# main.net
KiCad netlist of a schematic drawn in EAGLE
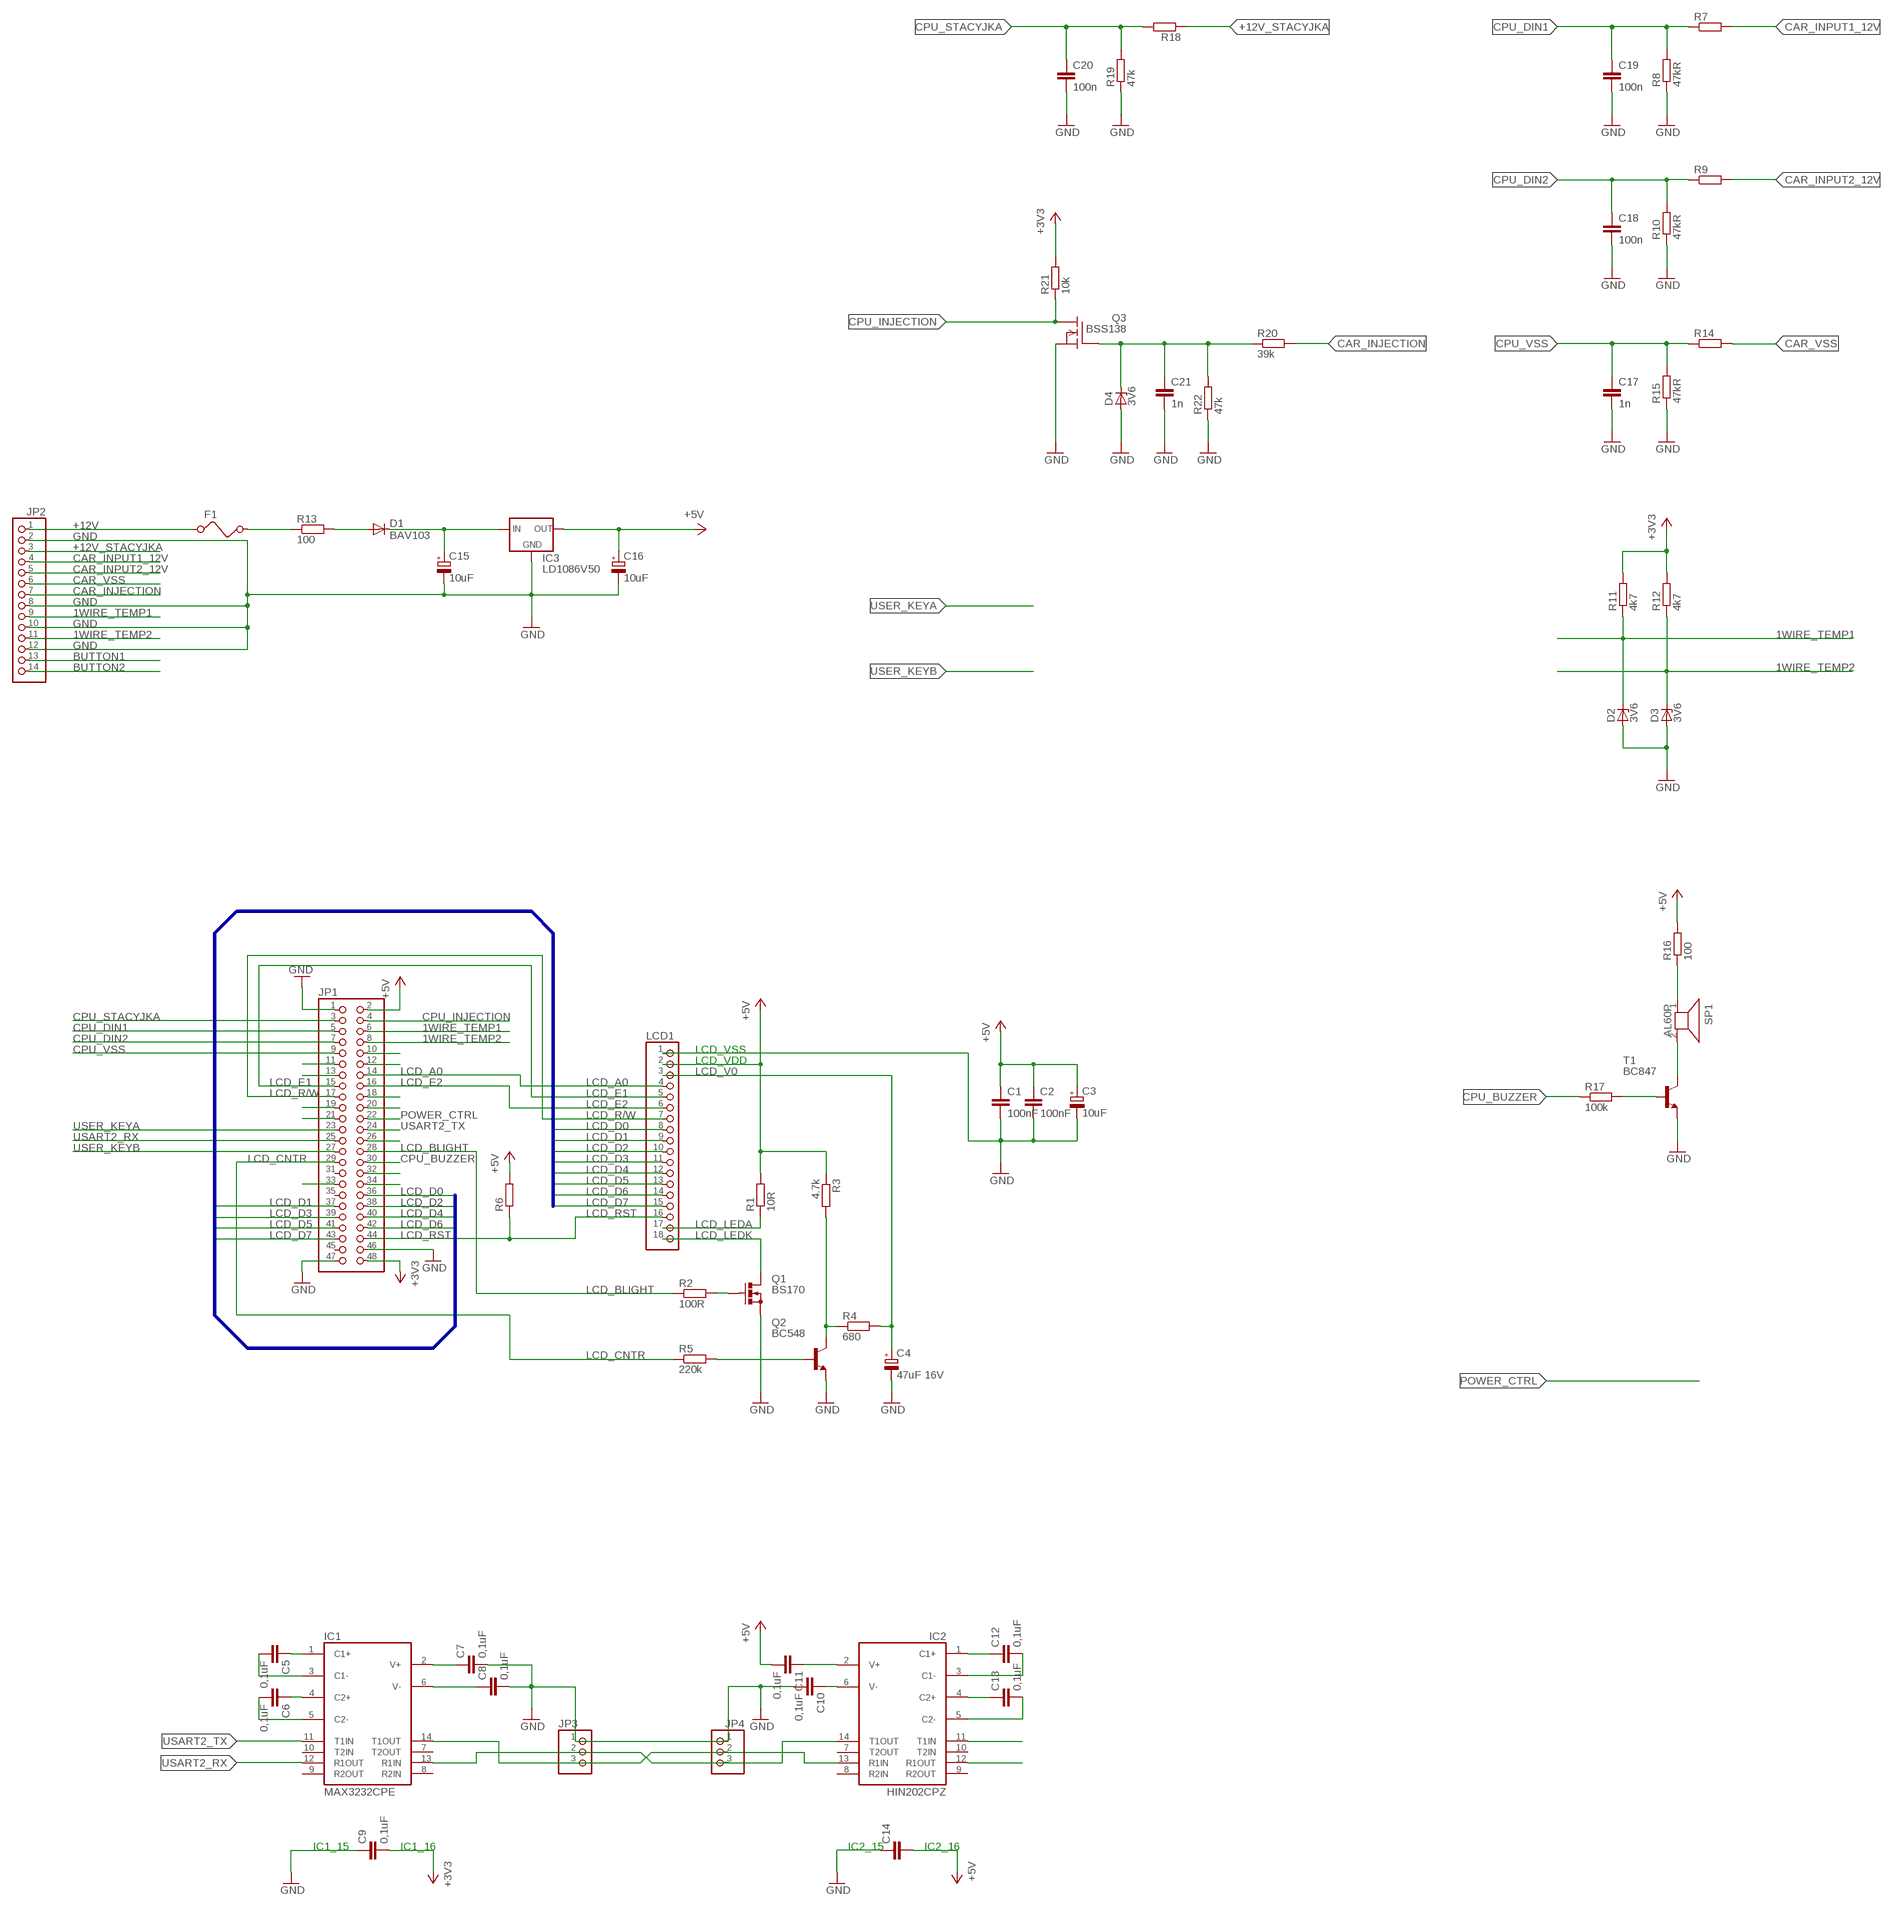
[diagram p0: schematic, sheet 1]

(export (version "E")
  (design (tool "Eeschema 10.0.6"))
  (components
    (comp (ref "C1")
      (value "100nF")
      (footprint "eagle-import:C025-024X044")
      (libsource (lib "eagle-import") (part "C-EU025-024X044"))
    )
    (comp (ref "C2")
      (value "100nF")
      (footprint "eagle-import:C025-024X044")
      (libsource (lib "eagle-import") (part "C-EU025-024X044"))
    )
    (comp (ref "C3")
      (value "10uF")
      (footprint "eagle-import:085CS_1AR")
      (libsource (lib "eagle-import") (part "CPOL-EU085CS-1AR"))
    )
    (comp (ref "C4")
      (value "47uF 16V")
      (footprint "eagle-import:085CS_1AR")
      (libsource (lib "eagle-import") (part "CPOL-EU085CS-1AR"))
    )
    (comp (ref "C5")
      (value "0,1uF")
      (footprint "eagle-import:C025-024X044")
      (libsource (lib "eagle-import") (part "C-EU025-024X044"))
    )
    (comp (ref "C6")
      (value "0,1uF")
      (footprint "eagle-import:C025-024X044")
      (libsource (lib "eagle-import") (part "C-EU025-024X044"))
    )
    (comp (ref "C7")
      (value "0,1uF")
      (footprint "eagle-import:C025-024X044")
      (libsource (lib "eagle-import") (part "C-EU025-024X044"))
    )
    (comp (ref "C8")
      (value "0,1uF")
      (footprint "eagle-import:C025-024X044")
      (libsource (lib "eagle-import") (part "C-EU025-024X044"))
    )
    (comp (ref "C9")
      (value "0,1uF")
      (footprint "eagle-import:C025-024X044")
      (libsource (lib "eagle-import") (part "C-EU025-024X044"))
    )
    (comp (ref "C10")
      (value "0,1uF")
      (footprint "eagle-import:C025-024X044")
      (libsource (lib "eagle-import") (part "C-EU025-024X044"))
    )
    (comp (ref "C11")
      (value "0,1uF")
      (footprint "eagle-import:C025-024X044")
      (libsource (lib "eagle-import") (part "C-EU025-024X044"))
    )
    (comp (ref "C12")
      (value "0,1uF")
      (footprint "eagle-import:C025-024X044")
      (libsource (lib "eagle-import") (part "C-EU025-024X044"))
    )
    (comp (ref "C13")
      (value "0,1uF")
      (footprint "eagle-import:C025-024X044")
      (libsource (lib "eagle-import") (part "C-EU025-024X044"))
    )
    (comp (ref "C14")
      (value "C-EU025-024X044")
      (footprint "eagle-import:C025-024X044")
      (libsource (lib "eagle-import") (part "C-EU025-024X044"))
    )
    (comp (ref "C15")
      (value "10uF")
      (footprint "eagle-import:085CS_1AR")
      (libsource (lib "eagle-import") (part "CPOL-EU085CS-1AR"))
    )
    (comp (ref "C16")
      (value "10uF")
      (footprint "eagle-import:085CS_1AR")
      (libsource (lib "eagle-import") (part "CPOL-EU085CS-1AR"))
    )
    (comp (ref "C17")
      (value "1n")
      (footprint "eagle-import:C025-024X044")
      (libsource (lib "eagle-import") (part "C-EU025-024X044"))
    )
    (comp (ref "C18")
      (value "100n")
      (footprint "eagle-import:C025-024X044")
      (libsource (lib "eagle-import") (part "C-EU025-024X044"))
    )
    (comp (ref "C19")
      (value "100n")
      (footprint "eagle-import:C025-024X044")
      (libsource (lib "eagle-import") (part "C-EU025-024X044"))
    )
    (comp (ref "C20")
      (value "100n")
      (footprint "eagle-import:C025-024X044")
      (libsource (lib "eagle-import") (part "C-EU025-024X044"))
    )
    (comp (ref "C21")
      (value "1n")
      (footprint "eagle-import:C025-024X044")
      (libsource (lib "eagle-import") (part "C-EU025-024X044"))
    )
    (comp (ref "D1")
      (value "BAV103")
      (footprint "eagle-import:DO41-10")
      (libsource (lib "eagle-import") (part "1N4004"))
    )
    (comp (ref "D2")
      (value "3V6")
      (footprint "eagle-import:C1702-15")
      (libsource (lib "eagle-import") (part "ZENER-DIODEC1702-15"))
    )
    (comp (ref "D3")
      (value "3V6")
      (footprint "eagle-import:C1702-15")
      (libsource (lib "eagle-import") (part "ZENER-DIODEC1702-15"))
    )
    (comp (ref "D4")
      (value "3V6")
      (footprint "eagle-import:C1702-15")
      (libsource (lib "eagle-import") (part "ZENER-DIODEC1702-15"))
    )
    (comp (ref "F1")
      (value "FUSE")
      (footprint "eagle-import:FUSE")
      (libsource (lib "eagle-import") (part "FUSE"))
    )
    (comp (ref "IC1")
      (value "MAX3232CPE")
      (footprint "eagle-import:DIL16")
      (fields (field (name "MF") "MAXIM") (field (name "MPN") "MAX3232CPE+"))
      (libsource (lib "eagle-import") (part "MAX3232PEC"))
    )
    (comp (ref "IC2")
      (value "HIN202CPZ")
      (footprint "eagle-import:DIL16")
      (fields (field (name "MF") "MAXIM") (field (name "MPN") "MAX3232CPE+"))
      (libsource (lib "eagle-import") (part "MAX3232PEC"))
    )
    (comp (ref "IC3")
      (value "LD1086V50")
      (footprint "eagle-import:78MXXL")
      (libsource (lib "eagle-import") (part "78MXXL"))
    )
    (comp (ref "JP1")
      (value "PINHD-2X24")
      (footprint "eagle-import:2X24")
      (libsource (lib "eagle-import") (part "PINHD-2X24"))
    )
    (comp (ref "JP2")
      (value "PINHD-1X14")
      (footprint "eagle-import:1X14")
      (libsource (lib "eagle-import") (part "PINHD-1X14"))
    )
    (comp (ref "JP3")
      (value "PINHD-1X3")
      (footprint "eagle-import:1X03")
      (libsource (lib "eagle-import") (part "PINHD-1X3"))
    )
    (comp (ref "JP4")
      (value "PINHD-1X3")
      (footprint "eagle-import:1X03")
      (libsource (lib "eagle-import") (part "PINHD-1X3"))
    )
    (comp (ref "LCD1")
      (value "PINHD-1X18")
      (footprint "eagle-import:1X18")
      (libsource (lib "eagle-import") (part "PINHD-1X18"))
    )
    (comp (ref "Q1")
      (value "BS170")
      (footprint "eagle-import:SOT54E")
      (libsource (lib "eagle-import") (part "BS170"))
    )
    (comp (ref "Q2")
      (value "BC548")
      (footprint "eagle-import:TO92-EBC")
      (libsource (lib "eagle-import") (part "BC548"))
    )
    (comp (ref "Q3")
      (value "BSS138")
      (footprint "eagle-import:TO92")
      (libsource (lib "eagle-import") (part "BSS101"))
    )
    (comp (ref "R1")
      (value "10R")
      (footprint "eagle-import:0204V")
      (libsource (lib "eagle-import") (part "R-EU_0204/2V"))
    )
    (comp (ref "R2")
      (value "100R")
      (footprint "eagle-import:0204V")
      (libsource (lib "eagle-import") (part "R-EU_0204/2V"))
    )
    (comp (ref "R3")
      (value "4.7k")
      (footprint "eagle-import:0204V")
      (libsource (lib "eagle-import") (part "R-EU_0204/2V"))
    )
    (comp (ref "R4")
      (value "680")
      (footprint "eagle-import:0204V")
      (libsource (lib "eagle-import") (part "R-EU_0204/2V"))
    )
    (comp (ref "R5")
      (value "220k")
      (footprint "eagle-import:0204V")
      (libsource (lib "eagle-import") (part "R-EU_0204/2V"))
    )
    (comp (ref "R6")
      (value "R-EU_0204/2V")
      (footprint "eagle-import:0204V")
      (libsource (lib "eagle-import") (part "R-EU_0204/2V"))
    )
    (comp (ref "R7")
      (value "R-EU_0204/2V")
      (footprint "eagle-import:0204V")
      (libsource (lib "eagle-import") (part "R-EU_0204/2V"))
    )
    (comp (ref "R8")
      (value "47kR")
      (footprint "eagle-import:0204V")
      (libsource (lib "eagle-import") (part "R-EU_0204/2V"))
    )
    (comp (ref "R9")
      (value "R-EU_0204/2V")
      (footprint "eagle-import:0204V")
      (libsource (lib "eagle-import") (part "R-EU_0204/2V"))
    )
    (comp (ref "R10")
      (value "47kR")
      (footprint "eagle-import:0204V")
      (libsource (lib "eagle-import") (part "R-EU_0204/2V"))
    )
    (comp (ref "R11")
      (value "4k7")
      (footprint "eagle-import:0204V")
      (libsource (lib "eagle-import") (part "R-EU_0204/2V"))
    )
    (comp (ref "R12")
      (value "4k7")
      (footprint "eagle-import:0204V")
      (libsource (lib "eagle-import") (part "R-EU_0204/2V"))
    )
    (comp (ref "R13")
      (value "100")
      (footprint "eagle-import:0204V")
      (libsource (lib "eagle-import") (part "R-EU_0204/2V"))
    )
    (comp (ref "R14")
      (value "R-EU_0204/2V")
      (footprint "eagle-import:0204V")
      (libsource (lib "eagle-import") (part "R-EU_0204/2V"))
    )
    (comp (ref "R15")
      (value "47kR")
      (footprint "eagle-import:0204V")
      (libsource (lib "eagle-import") (part "R-EU_0204/2V"))
    )
    (comp (ref "R16")
      (value "100")
      (footprint "eagle-import:0204V")
      (libsource (lib "eagle-import") (part "R-EU_0204/2V"))
    )
    (comp (ref "R17")
      (value "100k")
      (footprint "eagle-import:0204V")
      (libsource (lib "eagle-import") (part "R-EU_0204/2V"))
    )
    (comp (ref "R18")
      (value "R-EU_0204/2V")
      (footprint "eagle-import:0204V")
      (libsource (lib "eagle-import") (part "R-EU_0204/2V"))
    )
    (comp (ref "R19")
      (value "47k")
      (footprint "eagle-import:0204V")
      (libsource (lib "eagle-import") (part "R-EU_0204/2V"))
    )
    (comp (ref "R20")
      (value "39k")
      (footprint "eagle-import:0204V")
      (libsource (lib "eagle-import") (part "R-EU_0204/2V"))
    )
    (comp (ref "R21")
      (value "10k")
      (footprint "eagle-import:0204V")
      (libsource (lib "eagle-import") (part "R-EU_0204/2V"))
    )
    (comp (ref "R22")
      (value "47k")
      (footprint "eagle-import:0204V")
      (libsource (lib "eagle-import") (part "R-EU_0204/2V"))
    )
    (comp (ref "SP1")
      (value "AL60P")
      (footprint "eagle-import:AL60P")
      (libsource (lib "eagle-import") (part "AL60P"))
    )
    (comp (ref "T1")
      (value "BC847")
      (footprint "eagle-import:SOT23")
      (libsource (lib "eagle-import") (part "BC847"))
    )
  )
  (nets
    (net (code "1") (name "+3V3") (class "Default")
      (node (ref "C9") (pin "2") (pinfunction "2_2") (pintype "passive"))
      (node (ref "JP1") (pin "48") (pinfunction "48_48") (pintype "passive"))
      (node (ref "R11") (pin "2") (pinfunction "2_2") (pintype "passive"))
      (node (ref "R12") (pin "2") (pinfunction "2_2") (pintype "passive"))
      (node (ref "R21") (pin "2") (pinfunction "2_2") (pintype "passive"))
    )
    (net (code "2") (name "+5V") (class "Default")
      (node (ref "C1") (pin "1") (pinfunction "1_1") (pintype "passive"))
      (node (ref "C11") (pin "2") (pinfunction "2_2") (pintype "passive"))
      (node (ref "C14") (pin "2") (pinfunction "2_2") (pintype "passive"))
      (node (ref "C16") (pin "+") (pinfunction "+_+") (pintype "passive"))
      (node (ref "C2") (pin "1") (pinfunction "1_1") (pintype "passive"))
      (node (ref "C3") (pin "+") (pinfunction "+_+") (pintype "passive"))
      (node (ref "IC3") (pin "OUT") (pinfunction "OUT_OUT") (pintype "passive"))
      (node (ref "JP1") (pin "2") (pinfunction "2_2") (pintype "passive"))
      (node (ref "LCD1") (pin "2") (pinfunction "2_2") (pintype "passive"))
      (node (ref "R1") (pin "2") (pinfunction "2_2") (pintype "passive"))
      (node (ref "R16") (pin "2") (pinfunction "2_2") (pintype "passive"))
      (node (ref "R3") (pin "1") (pinfunction "1_1") (pintype "passive"))
      (node (ref "R6") (pin "2") (pinfunction "2_2") (pintype "passive"))
    )
    (net (code "3") (name "+12V_STACYJKA") (class "Default")
      (node (ref "JP2") (pin "3") (pinfunction "3_3") (pintype "passive"))
      (node (ref "R18") (pin "1") (pinfunction "1_1") (pintype "passive"))
    )
    (net (code "4") (name "/+12V") (class "Default")
      (node (ref "F1") (pin "1") (pinfunction "1_1") (pintype "passive"))
      (node (ref "JP2") (pin "1") (pinfunction "1_1") (pintype "passive"))
    )
    (net (code "5") (name "/1WIRE_TEMP1") (class "Default")
      (node (ref "D2") (pin "C") (pinfunction "C_C") (pintype "passive"))
      (node (ref "JP1") (pin "6") (pinfunction "6_6") (pintype "passive"))
      (node (ref "JP2") (pin "9") (pinfunction "9_9") (pintype "passive"))
      (node (ref "R11") (pin "1") (pinfunction "1_1") (pintype "passive"))
    )
    (net (code "6") (name "/1WIRE_TEMP2") (class "Default")
      (node (ref "D3") (pin "C") (pinfunction "C_C") (pintype "passive"))
      (node (ref "JP1") (pin "8") (pinfunction "8_8") (pintype "passive"))
      (node (ref "JP2") (pin "11") (pinfunction "11_11") (pintype "passive"))
      (node (ref "R12") (pin "1") (pinfunction "1_1") (pintype "passive"))
    )
    (net (code "7") (name "/BUTTON1") (class "Default")
      (node (ref "JP2") (pin "13") (pinfunction "13_13") (pintype "passive"))
    )
    (net (code "8") (name "/BUTTON2") (class "Default")
      (node (ref "JP2") (pin "14") (pinfunction "14_14") (pintype "passive"))
    )
    (net (code "9") (name "/LCD_A0") (class "Default")
      (node (ref "JP1") (pin "14") (pinfunction "14_14") (pintype "passive"))
      (node (ref "LCD1") (pin "4") (pinfunction "4_4") (pintype "passive"))
    )
    (net (code "10") (name "/LCD_BLIGHT") (class "Default")
      (node (ref "JP1") (pin "28") (pinfunction "28_28") (pintype "passive"))
      (node (ref "R2") (pin "1") (pinfunction "1_1") (pintype "passive"))
    )
    (net (code "11") (name "/LCD_CNTR") (class "Default")
      (node (ref "JP1") (pin "29") (pinfunction "29_29") (pintype "passive"))
      (node (ref "R5") (pin "1") (pinfunction "1_1") (pintype "passive"))
    )
    (net (code "12") (name "/LCD_D0") (class "Default")
      (node (ref "JP1") (pin "36") (pinfunction "36_36") (pintype "passive"))
      (node (ref "LCD1") (pin "8") (pinfunction "8_8") (pintype "passive"))
    )
    (net (code "13") (name "/LCD_D1") (class "Default")
      (node (ref "JP1") (pin "37") (pinfunction "37_37") (pintype "passive"))
      (node (ref "LCD1") (pin "9") (pinfunction "9_9") (pintype "passive"))
    )
    (net (code "14") (name "/LCD_D2") (class "Default")
      (node (ref "JP1") (pin "38") (pinfunction "38_38") (pintype "passive"))
      (node (ref "LCD1") (pin "10") (pinfunction "10_10") (pintype "passive"))
    )
    (net (code "15") (name "/LCD_D3") (class "Default")
      (node (ref "JP1") (pin "39") (pinfunction "39_39") (pintype "passive"))
      (node (ref "LCD1") (pin "11") (pinfunction "11_11") (pintype "passive"))
    )
    (net (code "16") (name "/LCD_D4") (class "Default")
      (node (ref "JP1") (pin "40") (pinfunction "40_40") (pintype "passive"))
      (node (ref "LCD1") (pin "12") (pinfunction "12_12") (pintype "passive"))
    )
    (net (code "17") (name "/LCD_D5") (class "Default")
      (node (ref "JP1") (pin "41") (pinfunction "41_41") (pintype "passive"))
      (node (ref "LCD1") (pin "13") (pinfunction "13_13") (pintype "passive"))
    )
    (net (code "18") (name "/LCD_D6") (class "Default")
      (node (ref "JP1") (pin "42") (pinfunction "42_42") (pintype "passive"))
      (node (ref "LCD1") (pin "14") (pinfunction "14_14") (pintype "passive"))
    )
    (net (code "19") (name "/LCD_D7") (class "Default")
      (node (ref "JP1") (pin "43") (pinfunction "43_43") (pintype "passive"))
      (node (ref "LCD1") (pin "15") (pinfunction "15_15") (pintype "passive"))
    )
    (net (code "20") (name "/LCD_E1") (class "Default")
      (node (ref "JP1") (pin "15") (pinfunction "15_15") (pintype "passive"))
      (node (ref "LCD1") (pin "5") (pinfunction "5_5") (pintype "passive"))
    )
    (net (code "21") (name "/LCD_E2") (class "Default")
      (node (ref "JP1") (pin "16") (pinfunction "16_16") (pintype "passive"))
      (node (ref "LCD1") (pin "6") (pinfunction "6_6") (pintype "passive"))
    )
    (net (code "22") (name "/LCD_LEDA") (class "Default")
      (node (ref "LCD1") (pin "17") (pinfunction "17_17") (pintype "passive"))
      (node (ref "R1") (pin "1") (pinfunction "1_1") (pintype "passive"))
    )
    (net (code "23") (name "/LCD_LEDK") (class "Default")
      (node (ref "LCD1") (pin "18") (pinfunction "18_18") (pintype "passive"))
      (node (ref "Q1") (pin "D") (pinfunction "D_D") (pintype "passive"))
    )
    (net (code "24") (name "/LCD_RST") (class "Default")
      (node (ref "JP1") (pin "44") (pinfunction "44_44") (pintype "passive"))
      (node (ref "LCD1") (pin "16") (pinfunction "16_16") (pintype "passive"))
      (node (ref "R6") (pin "1") (pinfunction "1_1") (pintype "passive"))
    )
    (net (code "25") (name "/LCD_R{slash}W") (class "Default")
      (node (ref "JP1") (pin "17") (pinfunction "17_17") (pintype "passive"))
      (node (ref "LCD1") (pin "7") (pinfunction "7_7") (pintype "passive"))
    )
    (net (code "26") (name "/LCD_V0") (class "Default")
      (node (ref "C4") (pin "+") (pinfunction "+_+") (pintype "passive"))
      (node (ref "LCD1") (pin "3") (pinfunction "3_3") (pintype "passive"))
      (node (ref "R4") (pin "2") (pinfunction "2_2") (pintype "passive"))
    )
    (net (code "27") (name "CAR_INJECTION") (class "Default")
      (node (ref "JP2") (pin "7") (pinfunction "7_7") (pintype "passive"))
      (node (ref "R20") (pin "2") (pinfunction "2_2") (pintype "passive"))
    )
    (net (code "28") (name "CAR_INPUT1_12V") (class "Default")
      (node (ref "JP2") (pin "4") (pinfunction "4_4") (pintype "passive"))
      (node (ref "R7") (pin "2") (pinfunction "2_2") (pintype "passive"))
    )
    (net (code "29") (name "CAR_INPUT2_12V") (class "Default")
      (node (ref "JP2") (pin "5") (pinfunction "5_5") (pintype "passive"))
      (node (ref "R9") (pin "2") (pinfunction "2_2") (pintype "passive"))
    )
    (net (code "30") (name "CAR_VSS") (class "Default")
      (node (ref "JP2") (pin "6") (pinfunction "6_6") (pintype "passive"))
      (node (ref "R14") (pin "2") (pinfunction "2_2") (pintype "passive"))
    )
    (net (code "31") (name "CPU_BUZZER") (class "Default")
      (node (ref "JP1") (pin "30") (pinfunction "30_30") (pintype "passive"))
      (node (ref "R17") (pin "1") (pinfunction "1_1") (pintype "passive"))
    )
    (net (code "32") (name "CPU_DIN1") (class "Default")
      (node (ref "C19") (pin "1") (pinfunction "1_1") (pintype "passive"))
      (node (ref "JP1") (pin "5") (pinfunction "5_5") (pintype "passive"))
      (node (ref "R7") (pin "1") (pinfunction "1_1") (pintype "passive"))
      (node (ref "R8") (pin "2") (pinfunction "2_2") (pintype "passive"))
    )
    (net (code "33") (name "CPU_DIN2") (class "Default")
      (node (ref "C18") (pin "1") (pinfunction "1_1") (pintype "passive"))
      (node (ref "JP1") (pin "7") (pinfunction "7_7") (pintype "passive"))
      (node (ref "R10") (pin "2") (pinfunction "2_2") (pintype "passive"))
      (node (ref "R9") (pin "1") (pinfunction "1_1") (pintype "passive"))
    )
    (net (code "34") (name "CPU_INJECTION") (class "Default")
      (node (ref "JP1") (pin "4") (pinfunction "4_4") (pintype "passive"))
      (node (ref "Q3") (pin "3") (pinfunction "D_3") (pintype "passive"))
      (node (ref "R21") (pin "1") (pinfunction "1_1") (pintype "passive"))
    )
    (net (code "35") (name "CPU_STACYJKA") (class "Default")
      (node (ref "C20") (pin "1") (pinfunction "1_1") (pintype "passive"))
      (node (ref "JP1") (pin "3") (pinfunction "3_3") (pintype "passive"))
      (node (ref "R18") (pin "2") (pinfunction "2_2") (pintype "passive"))
      (node (ref "R19") (pin "2") (pinfunction "2_2") (pintype "passive"))
    )
    (net (code "36") (name "CPU_VSS") (class "Default")
      (node (ref "C17") (pin "1") (pinfunction "1_1") (pintype "passive"))
      (node (ref "JP1") (pin "9") (pinfunction "9_9") (pintype "passive"))
      (node (ref "R14") (pin "1") (pinfunction "1_1") (pintype "passive"))
      (node (ref "R15") (pin "2") (pinfunction "2_2") (pintype "passive"))
    )
    (net (code "37") (name "GND") (class "Default")
      (node (ref "C1") (pin "2") (pinfunction "2_2") (pintype "passive"))
      (node (ref "C10") (pin "2") (pinfunction "2_2") (pintype "passive"))
      (node (ref "C14") (pin "1") (pinfunction "1_1") (pintype "passive"))
      (node (ref "C15") (pin "-") (pinfunction "-_-") (pintype "passive"))
      (node (ref "C16") (pin "-") (pinfunction "-_-") (pintype "passive"))
      (node (ref "C17") (pin "2") (pinfunction "2_2") (pintype "passive"))
      (node (ref "C18") (pin "2") (pinfunction "2_2") (pintype "passive"))
      (node (ref "C19") (pin "2") (pinfunction "2_2") (pintype "passive"))
      (node (ref "C2") (pin "2") (pinfunction "2_2") (pintype "passive"))
      (node (ref "C20") (pin "2") (pinfunction "2_2") (pintype "passive"))
      (node (ref "C21") (pin "2") (pinfunction "2_2") (pintype "passive"))
      (node (ref "C3") (pin "-") (pinfunction "-_-") (pintype "passive"))
      (node (ref "C4") (pin "-") (pinfunction "-_-") (pintype "passive"))
      (node (ref "C7") (pin "2") (pinfunction "2_2") (pintype "passive"))
      (node (ref "C8") (pin "2") (pinfunction "2_2") (pintype "passive"))
      (node (ref "C9") (pin "1") (pinfunction "1_1") (pintype "passive"))
      (node (ref "D2") (pin "A") (pinfunction "A_A") (pintype "passive"))
      (node (ref "D3") (pin "A") (pinfunction "A_A") (pintype "passive"))
      (node (ref "D4") (pin "A") (pinfunction "A_A") (pintype "passive"))
      (node (ref "IC3") (pin "GND") (pinfunction "GND_GND") (pintype "input"))
      (node (ref "JP1") (pin "1") (pinfunction "1_1") (pintype "passive"))
      (node (ref "JP1") (pin "46") (pinfunction "46_46") (pintype "passive"))
      (node (ref "JP1") (pin "47") (pinfunction "47_47") (pintype "passive"))
      (node (ref "JP2") (pin "10") (pinfunction "10_10") (pintype "passive"))
      (node (ref "JP2") (pin "12") (pinfunction "12_12") (pintype "passive"))
      (node (ref "JP2") (pin "2") (pinfunction "2_2") (pintype "passive"))
      (node (ref "JP2") (pin "8") (pinfunction "8_8") (pintype "passive"))
      (node (ref "JP3") (pin "1") (pinfunction "1_1") (pintype "passive"))
      (node (ref "JP4") (pin "1") (pinfunction "1_1") (pintype "passive"))
      (node (ref "LCD1") (pin "1") (pinfunction "1_1") (pintype "passive"))
      (node (ref "Q1") (pin "S") (pinfunction "S_S") (pintype "passive"))
      (node (ref "Q2") (pin "E") (pinfunction "E_E") (pintype "passive"))
      (node (ref "Q3") (pin "1") (pinfunction "S_1") (pintype "passive"))
      (node (ref "R10") (pin "1") (pinfunction "1_1") (pintype "passive"))
      (node (ref "R15") (pin "1") (pinfunction "1_1") (pintype "passive"))
      (node (ref "R19") (pin "1") (pinfunction "1_1") (pintype "passive"))
      (node (ref "R22") (pin "1") (pinfunction "1_1") (pintype "passive"))
      (node (ref "R8") (pin "1") (pinfunction "1_1") (pintype "passive"))
      (node (ref "T1") (pin "2") (pinfunction "E_2") (pintype "passive"))
    )
    (net (code "38") (name "Net-(C15-Pad+)") (class "Default")
      (node (ref "C15") (pin "+") (pinfunction "+_+") (pintype "passive"))
      (node (ref "D1") (pin "C") (pinfunction "C_C") (pintype "passive"))
      (node (ref "IC3") (pin "IN") (pinfunction "IN_IN") (pintype "input"))
    )
    (net (code "39") (name "Net-(D1-PadA)") (class "Default")
      (node (ref "D1") (pin "A") (pinfunction "A_A") (pintype "passive"))
      (node (ref "R13") (pin "2") (pinfunction "2_2") (pintype "passive"))
    )
    (net (code "40") (name "Net-(F1-Pad2)") (class "Default")
      (node (ref "F1") (pin "2") (pinfunction "2_2") (pintype "passive"))
      (node (ref "R13") (pin "1") (pinfunction "1_1") (pintype "passive"))
    )
    (net (code "41") (name "Net-(IC1A-C1+)") (class "Default")
      (node (ref "C5") (pin "1") (pinfunction "1_1") (pintype "passive"))
      (node (ref "IC1") (pin "1") (pinfunction "C1+_1") (pintype "bidirectional"))
    )
    (net (code "42") (name "Net-(IC1A-C1-)") (class "Default")
      (node (ref "C5") (pin "2") (pinfunction "2_2") (pintype "passive"))
      (node (ref "IC1") (pin "3") (pinfunction "C1-_3") (pintype "bidirectional"))
    )
    (net (code "43") (name "Net-(IC1A-C2+)") (class "Default")
      (node (ref "C6") (pin "1") (pinfunction "1_1") (pintype "passive"))
      (node (ref "IC1") (pin "4") (pinfunction "C2+_4") (pintype "bidirectional"))
    )
    (net (code "44") (name "Net-(IC1A-C2-)") (class "Default")
      (node (ref "C6") (pin "2") (pinfunction "2_2") (pintype "passive"))
      (node (ref "IC1") (pin "5") (pinfunction "C2-_5") (pintype "bidirectional"))
    )
    (net (code "45") (name "Net-(IC1A-R1IN)") (class "Default")
      (node (ref "IC1") (pin "13") (pinfunction "R1IN_13") (pintype "input"))
      (node (ref "IC2") (pin "14") (pinfunction "T1OUT_14") (pintype "output"))
      (node (ref "JP3") (pin "2") (pinfunction "2_2") (pintype "passive"))
      (node (ref "JP4") (pin "3") (pinfunction "3_3") (pintype "passive"))
    )
    (net (code "46") (name "Net-(IC1A-T1OUT)") (class "Default")
      (node (ref "IC1") (pin "14") (pinfunction "T1OUT_14") (pintype "output"))
      (node (ref "IC2") (pin "13") (pinfunction "R1IN_13") (pintype "input"))
      (node (ref "JP3") (pin "3") (pinfunction "3_3") (pintype "passive"))
      (node (ref "JP4") (pin "2") (pinfunction "2_2") (pintype "passive"))
    )
    (net (code "47") (name "Net-(IC1A-V+)") (class "Default")
      (node (ref "C7") (pin "1") (pinfunction "1_1") (pintype "passive"))
      (node (ref "IC1") (pin "2") (pinfunction "V+_2") (pintype "bidirectional"))
    )
    (net (code "48") (name "Net-(IC1A-V-)") (class "Default")
      (node (ref "C8") (pin "1") (pinfunction "1_1") (pintype "passive"))
      (node (ref "IC1") (pin "6") (pinfunction "V-_6") (pintype "bidirectional"))
    )
    (net (code "49") (name "Net-(IC2A-C1+)") (class "Default")
      (node (ref "C12") (pin "1") (pinfunction "1_1") (pintype "passive"))
      (node (ref "IC2") (pin "1") (pinfunction "C1+_1") (pintype "bidirectional"))
    )
    (net (code "50") (name "Net-(IC2A-C1-)") (class "Default")
      (node (ref "C12") (pin "2") (pinfunction "2_2") (pintype "passive"))
      (node (ref "IC2") (pin "3") (pinfunction "C1-_3") (pintype "bidirectional"))
    )
    (net (code "51") (name "Net-(IC2A-C2+)") (class "Default")
      (node (ref "C13") (pin "1") (pinfunction "1_1") (pintype "passive"))
      (node (ref "IC2") (pin "4") (pinfunction "C2+_4") (pintype "bidirectional"))
    )
    (net (code "52") (name "Net-(IC2A-C2-)") (class "Default")
      (node (ref "C13") (pin "2") (pinfunction "2_2") (pintype "passive"))
      (node (ref "IC2") (pin "5") (pinfunction "C2-_5") (pintype "bidirectional"))
    )
    (net (code "53") (name "Net-(IC2A-V+)") (class "Default")
      (node (ref "C11") (pin "1") (pinfunction "1_1") (pintype "passive"))
      (node (ref "IC2") (pin "2") (pinfunction "V+_2") (pintype "bidirectional"))
    )
    (net (code "54") (name "Net-(IC2A-V-)") (class "Default")
      (node (ref "C10") (pin "1") (pinfunction "1_1") (pintype "passive"))
      (node (ref "IC2") (pin "6") (pinfunction "V-_6") (pintype "bidirectional"))
    )
    (net (code "55") (name "Net-(Q1-PadG)") (class "Default")
      (node (ref "Q1") (pin "G") (pinfunction "G_G") (pintype "passive"))
      (node (ref "R2") (pin "2") (pinfunction "2_2") (pintype "passive"))
    )
    (net (code "56") (name "Net-(Q2-PadB)") (class "Default")
      (node (ref "Q2") (pin "B") (pinfunction "B_B") (pintype "passive"))
      (node (ref "R5") (pin "2") (pinfunction "2_2") (pintype "passive"))
    )
    (net (code "57") (name "Net-(Q2-PadC)") (class "Default")
      (node (ref "Q2") (pin "C") (pinfunction "C_C") (pintype "passive"))
      (node (ref "R3") (pin "2") (pinfunction "2_2") (pintype "passive"))
      (node (ref "R4") (pin "1") (pinfunction "1_1") (pintype "passive"))
    )
    (net (code "58") (name "Net-(Q3-G)") (class "Default")
      (node (ref "C21") (pin "1") (pinfunction "1_1") (pintype "passive"))
      (node (ref "D4") (pin "C") (pinfunction "C_C") (pintype "passive"))
      (node (ref "Q3") (pin "2") (pinfunction "G_2") (pintype "passive"))
      (node (ref "R20") (pin "1") (pinfunction "1_1") (pintype "passive"))
      (node (ref "R22") (pin "2") (pinfunction "2_2") (pintype "passive"))
    )
    (net (code "59") (name "Net-(R16-Pad1)") (class "Default")
      (node (ref "R16") (pin "1") (pinfunction "1_1") (pintype "passive"))
      (node (ref "SP1") (pin "1") (pinfunction "1_1") (pintype "passive"))
    )
    (net (code "60") (name "Net-(T1-B)") (class "Default")
      (node (ref "R17") (pin "2") (pinfunction "2_2") (pintype "passive"))
      (node (ref "T1") (pin "1") (pinfunction "B_1") (pintype "passive"))
    )
    (net (code "61") (name "Net-(T1-C)") (class "Default")
      (node (ref "SP1") (pin "2") (pinfunction "2_2") (pintype "passive"))
      (node (ref "T1") (pin "3") (pinfunction "C_3") (pintype "passive"))
    )
    (net (code "62") (name "POWER_CTRL") (class "Default")
      (node (ref "JP1") (pin "22") (pinfunction "22_22") (pintype "passive"))
    )
    (net (code "63") (name "USART2_RX") (class "Default")
      (node (ref "IC1") (pin "12") (pinfunction "R1OUT_12") (pintype "output"))
      (node (ref "JP1") (pin "25") (pinfunction "25_25") (pintype "passive"))
    )
    (net (code "64") (name "USART2_TX") (class "Default")
      (node (ref "IC1") (pin "11") (pinfunction "T1IN_11") (pintype "input"))
      (node (ref "JP1") (pin "24") (pinfunction "24_24") (pintype "passive"))
    )
    (net (code "65") (name "USER_KEYA") (class "Default")
      (node (ref "JP1") (pin "23") (pinfunction "23_23") (pintype "passive"))
    )
    (net (code "66") (name "USER_KEYB") (class "Default")
      (node (ref "JP1") (pin "27") (pinfunction "27_27") (pintype "passive"))
    )
    (net (code "67") (name "unconnected-(IC1A-R2IN-Pad8)") (class "Default")
      (node (ref "IC1") (pin "8") (pinfunction "R2IN_8") (pintype "input"))
    )
    (net (code "68") (name "unconnected-(IC1A-R2OUT-Pad9)") (class "Default")
      (node (ref "IC1") (pin "9") (pinfunction "R2OUT_9") (pintype "output"))
    )
    (net (code "69") (name "unconnected-(IC1A-T2IN-Pad10)") (class "Default")
      (node (ref "IC1") (pin "10") (pinfunction "T2IN_10") (pintype "input"))
    )
    (net (code "70") (name "unconnected-(IC1A-T2OUT-Pad7)") (class "Default")
      (node (ref "IC1") (pin "7") (pinfunction "T2OUT_7") (pintype "output"))
    )
    (net (code "71") (name "unconnected-(IC2A-R1OUT-Pad12)") (class "Default")
      (node (ref "IC2") (pin "12") (pinfunction "R1OUT_12") (pintype "output"))
    )
    (net (code "72") (name "unconnected-(IC2A-R2IN-Pad8)") (class "Default")
      (node (ref "IC2") (pin "8") (pinfunction "R2IN_8") (pintype "input"))
    )
    (net (code "73") (name "unconnected-(IC2A-R2OUT-Pad9)") (class "Default")
      (node (ref "IC2") (pin "9") (pinfunction "R2OUT_9") (pintype "output"))
    )
    (net (code "74") (name "unconnected-(IC2A-T1IN-Pad11)") (class "Default")
      (node (ref "IC2") (pin "11") (pinfunction "T1IN_11") (pintype "input"))
    )
    (net (code "75") (name "unconnected-(IC2A-T2IN-Pad10)") (class "Default")
      (node (ref "IC2") (pin "10") (pinfunction "T2IN_10") (pintype "input"))
    )
    (net (code "76") (name "unconnected-(IC2A-T2OUT-Pad7)") (class "Default")
      (node (ref "IC2") (pin "7") (pinfunction "T2OUT_7") (pintype "output"))
    )
    (net (code "77") (name "unconnected-(JP1-Pad10)") (class "Default")
      (node (ref "JP1") (pin "10") (pinfunction "10_10") (pintype "passive"))
    )
    (net (code "78") (name "unconnected-(JP1-Pad11)") (class "Default")
      (node (ref "JP1") (pin "11") (pinfunction "11_11") (pintype "passive"))
    )
    (net (code "79") (name "unconnected-(JP1-Pad12)") (class "Default")
      (node (ref "JP1") (pin "12") (pinfunction "12_12") (pintype "passive"))
    )
    (net (code "80") (name "unconnected-(JP1-Pad13)") (class "Default")
      (node (ref "JP1") (pin "13") (pinfunction "13_13") (pintype "passive"))
    )
    (net (code "81") (name "unconnected-(JP1-Pad18)") (class "Default")
      (node (ref "JP1") (pin "18") (pinfunction "18_18") (pintype "passive"))
    )
    (net (code "82") (name "unconnected-(JP1-Pad19)") (class "Default")
      (node (ref "JP1") (pin "19") (pinfunction "19_19") (pintype "passive"))
    )
    (net (code "83") (name "unconnected-(JP1-Pad20)") (class "Default")
      (node (ref "JP1") (pin "20") (pinfunction "20_20") (pintype "passive"))
    )
    (net (code "84") (name "unconnected-(JP1-Pad21)") (class "Default")
      (node (ref "JP1") (pin "21") (pinfunction "21_21") (pintype "passive"))
    )
    (net (code "85") (name "unconnected-(JP1-Pad26)") (class "Default")
      (node (ref "JP1") (pin "26") (pinfunction "26_26") (pintype "passive"))
    )
    (net (code "86") (name "unconnected-(JP1-Pad31)") (class "Default")
      (node (ref "JP1") (pin "31") (pinfunction "31_31") (pintype "passive"))
    )
    (net (code "87") (name "unconnected-(JP1-Pad32)") (class "Default")
      (node (ref "JP1") (pin "32") (pinfunction "32_32") (pintype "passive"))
    )
    (net (code "88") (name "unconnected-(JP1-Pad33)") (class "Default")
      (node (ref "JP1") (pin "33") (pinfunction "33_33") (pintype "passive"))
    )
    (net (code "89") (name "unconnected-(JP1-Pad34)") (class "Default")
      (node (ref "JP1") (pin "34") (pinfunction "34_34") (pintype "passive"))
    )
    (net (code "90") (name "unconnected-(JP1-Pad35)") (class "Default")
      (node (ref "JP1") (pin "35") (pinfunction "35_35") (pintype "passive"))
    )
    (net (code "91") (name "unconnected-(JP1-Pad45)") (class "Default")
      (node (ref "JP1") (pin "45") (pinfunction "45_45") (pintype "passive"))
    )
  )
)
